# light.net
KiCad netlist of a schematic drawn in EAGLE
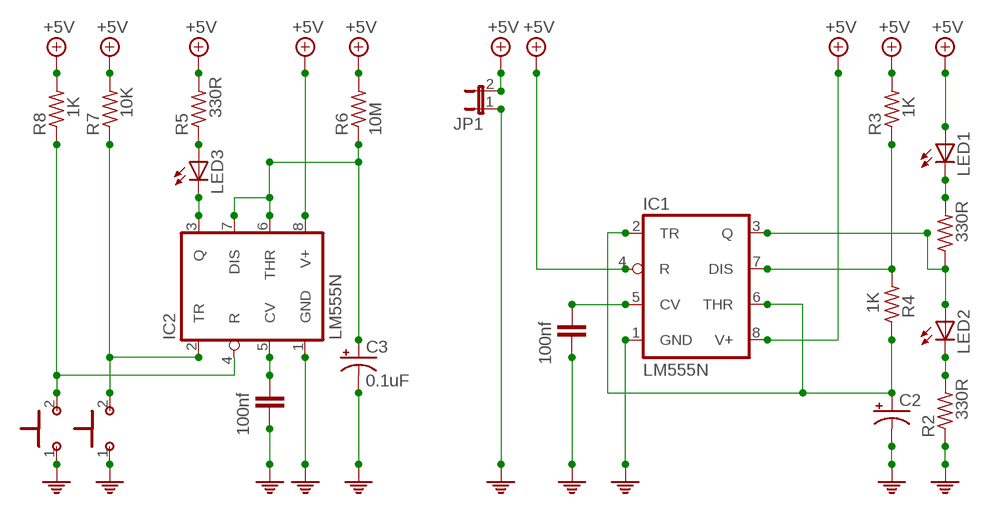
[diagram p0: schematic, sheet 1]

(export (version "E")
  (design (tool "Eeschema 10.0.6"))
  (components
    (comp (ref "C1")
      (value "100nf")
      (footprint "eagle-import:C050-025X075")
      (libsource (lib "eagle-import") (part "C-EU050-025X075"))
    )
    (comp (ref "C2")
      (value "CPOL-USE5-9VAXIAL")
      (footprint "eagle-import:E5R")
      (libsource (lib "eagle-import") (part "CPOL-USE5-9VAXIAL"))
    )
    (comp (ref "C3")
      (value "0.1uF")
      (footprint "eagle-import:E5R")
      (libsource (lib "eagle-import") (part "CPOL-USE5-9VAXIAL"))
    )
    (comp (ref "C4")
      (value "100nf")
      (footprint "eagle-import:C050-025X075")
      (libsource (lib "eagle-import") (part "C-EU050-025X075"))
    )
    (comp (ref "IC1")
      (value "LM555N")
      (footprint "eagle-import:DIL08")
      (libsource (lib "eagle-import") (part "555NLM"))
    )
    (comp (ref "IC2")
      (value "LM555N")
      (footprint "eagle-import:DIL08")
      (libsource (lib "eagle-import") (part "555NLM"))
    )
    (comp (ref "JP1")
      (value "JP1E")
      (footprint "eagle-import:JP1")
      (libsource (lib "eagle-import") (part "JP1E"))
    )
    (comp (ref "LED1")
      (value "LED5MM")
      (footprint "eagle-import:LED5MM")
      (libsource (lib "eagle-import") (part "LED5MM"))
    )
    (comp (ref "LED2")
      (value "LED5MM")
      (footprint "eagle-import:LED5MM")
      (libsource (lib "eagle-import") (part "LED5MM"))
    )
    (comp (ref "LED3")
      (value "LED5MM")
      (footprint "eagle-import:LED5MM")
      (libsource (lib "eagle-import") (part "LED5MM"))
    )
    (comp (ref "R1")
      (value "330R")
      (footprint "eagle-import:0207_10")
      (libsource (lib "eagle-import") (part "R-US_0207/10"))
    )
    (comp (ref "R2")
      (value "330R")
      (footprint "eagle-import:0207_10")
      (libsource (lib "eagle-import") (part "R-US_0207/10"))
    )
    (comp (ref "R3")
      (value "1K")
      (footprint "eagle-import:0207_10")
      (libsource (lib "eagle-import") (part "R-US_0207/10"))
    )
    (comp (ref "R4")
      (value "1K")
      (footprint "eagle-import:0207_10")
      (libsource (lib "eagle-import") (part "R-US_0207/10"))
    )
    (comp (ref "R5")
      (value "330R")
      (footprint "eagle-import:0207_10")
      (libsource (lib "eagle-import") (part "R-US_0207/10"))
    )
    (comp (ref "R6")
      (value "10M")
      (footprint "eagle-import:0207_10")
      (libsource (lib "eagle-import") (part "R-US_0207/10"))
    )
    (comp (ref "R7")
      (value "10K")
      (footprint "eagle-import:0207_10")
      (libsource (lib "eagle-import") (part "R-US_0207/10"))
    )
    (comp (ref "R8")
      (value "1K")
      (footprint "eagle-import:0207_10")
      (libsource (lib "eagle-import") (part "R-US_0207/10"))
    )
    (comp (ref "U$1")
      (value "PUSHBUTTON")
      (footprint "eagle-import:PUSHBUTTON")
      (libsource (lib "eagle-import") (part "PUSHBUTTON"))
    )
    (comp (ref "U$2")
      (value "PUSHBUTTON")
      (footprint "eagle-import:PUSHBUTTON")
      (libsource (lib "eagle-import") (part "PUSHBUTTON"))
    )
  )
  (nets
    (net (code "1") (name "+5V") (class "Default")
      (node (ref "IC1") (pin "4") (pinfunction "R_4") (pintype "input"))
      (node (ref "IC1") (pin "8") (pinfunction "V+_8") (pintype "power_in"))
      (node (ref "IC2") (pin "8") (pinfunction "V+_8") (pintype "power_in"))
      (node (ref "JP1") (pin "2") (pinfunction "2_2") (pintype "passive"))
      (node (ref "LED1") (pin "A") (pinfunction "A_A") (pintype "passive"))
      (node (ref "R3") (pin "2") (pinfunction "2_2") (pintype "passive"))
      (node (ref "R5") (pin "2") (pinfunction "2_2") (pintype "passive"))
      (node (ref "R6") (pin "2") (pinfunction "2_2") (pintype "passive"))
      (node (ref "R7") (pin "2") (pinfunction "2_2") (pintype "passive"))
      (node (ref "R8") (pin "2") (pinfunction "2_2") (pintype "passive"))
    )
    (net (code "2") (name "Net-(IC1-CV)") (class "Default")
      (node (ref "C1") (pin "1") (pinfunction "1_1") (pintype "passive"))
      (node (ref "IC1") (pin "5") (pinfunction "CV_5") (pintype "input"))
    )
    (net (code "3") (name "Net-(IC1-DIS)") (class "Default")
      (node (ref "IC1") (pin "7") (pinfunction "DIS_7") (pintype "input"))
      (node (ref "R3") (pin "1") (pinfunction "1_1") (pintype "passive"))
      (node (ref "R4") (pin "2") (pinfunction "2_2") (pintype "passive"))
    )
    (net (code "4") (name "Net-(IC1-Q)") (class "Default")
      (node (ref "IC1") (pin "3") (pinfunction "Q_3") (pintype "output"))
      (node (ref "LED2") (pin "A") (pinfunction "A_A") (pintype "passive"))
      (node (ref "R1") (pin "1") (pinfunction "1_1") (pintype "passive"))
    )
    (net (code "5") (name "Net-(IC1-THR)") (class "Default")
      (node (ref "C2") (pin "+") (pinfunction "+_+") (pintype "passive"))
      (node (ref "IC1") (pin "2") (pinfunction "TR_2") (pintype "input"))
      (node (ref "IC1") (pin "6") (pinfunction "THR_6") (pintype "input"))
      (node (ref "R4") (pin "1") (pinfunction "1_1") (pintype "passive"))
    )
    (net (code "6") (name "Net-(IC2-CV)") (class "Default")
      (node (ref "C4") (pin "1") (pinfunction "1_1") (pintype "passive"))
      (node (ref "IC2") (pin "5") (pinfunction "CV_5") (pintype "input"))
    )
    (net (code "7") (name "Net-(IC2-DIS)") (class "Default")
      (node (ref "C3") (pin "+") (pinfunction "+_+") (pintype "passive"))
      (node (ref "IC2") (pin "6") (pinfunction "THR_6") (pintype "input"))
      (node (ref "IC2") (pin "7") (pinfunction "DIS_7") (pintype "input"))
      (node (ref "R6") (pin "1") (pinfunction "1_1") (pintype "passive"))
    )
    (net (code "8") (name "Net-(IC2-Q)") (class "Default")
      (node (ref "IC2") (pin "3") (pinfunction "Q_3") (pintype "output"))
      (node (ref "LED3") (pin "K") (pinfunction "C_K") (pintype "passive"))
    )
    (net (code "9") (name "Net-(IC2-R)") (class "Default")
      (node (ref "IC2") (pin "4") (pinfunction "R_4") (pintype "input"))
      (node (ref "R8") (pin "1") (pinfunction "1_1") (pintype "passive"))
      (node (ref "U$2") (pin "2") (pinfunction "2_2") (pintype "bidirectional"))
    )
    (net (code "10") (name "Net-(IC2-TR)") (class "Default")
      (node (ref "IC2") (pin "2") (pinfunction "TR_2") (pintype "input"))
      (node (ref "R7") (pin "1") (pinfunction "1_1") (pintype "passive"))
      (node (ref "U$1") (pin "2") (pinfunction "2_2") (pintype "bidirectional"))
    )
    (net (code "11") (name "Net-(LED1-C)") (class "Default")
      (node (ref "LED1") (pin "K") (pinfunction "C_K") (pintype "passive"))
      (node (ref "R1") (pin "2") (pinfunction "2_2") (pintype "passive"))
    )
    (net (code "12") (name "Net-(LED2-C)") (class "Default")
      (node (ref "LED2") (pin "K") (pinfunction "C_K") (pintype "passive"))
      (node (ref "R2") (pin "2") (pinfunction "2_2") (pintype "passive"))
    )
    (net (code "13") (name "Net-(LED3-PadA)") (class "Default")
      (node (ref "LED3") (pin "A") (pinfunction "A_A") (pintype "passive"))
      (node (ref "R5") (pin "1") (pinfunction "1_1") (pintype "passive"))
    )
    (net (code "14") (name "PE") (class "Default")
      (node (ref "C1") (pin "2") (pinfunction "2_2") (pintype "passive"))
      (node (ref "C2") (pin "-") (pinfunction "-_-") (pintype "passive"))
      (node (ref "C3") (pin "-") (pinfunction "-_-") (pintype "passive"))
      (node (ref "C4") (pin "2") (pinfunction "2_2") (pintype "passive"))
      (node (ref "IC1") (pin "1") (pinfunction "GND_1") (pintype "power_in"))
      (node (ref "IC2") (pin "1") (pinfunction "GND_1") (pintype "power_in"))
      (node (ref "JP1") (pin "1") (pinfunction "1_1") (pintype "passive"))
      (node (ref "R2") (pin "1") (pinfunction "1_1") (pintype "passive"))
      (node (ref "U$1") (pin "1") (pinfunction "1_1") (pintype "bidirectional"))
      (node (ref "U$2") (pin "1") (pinfunction "1_1") (pintype "bidirectional"))
    )
  )
)
